# 3-21.net
KiCad netlist of a schematic drawn in Altium Designer
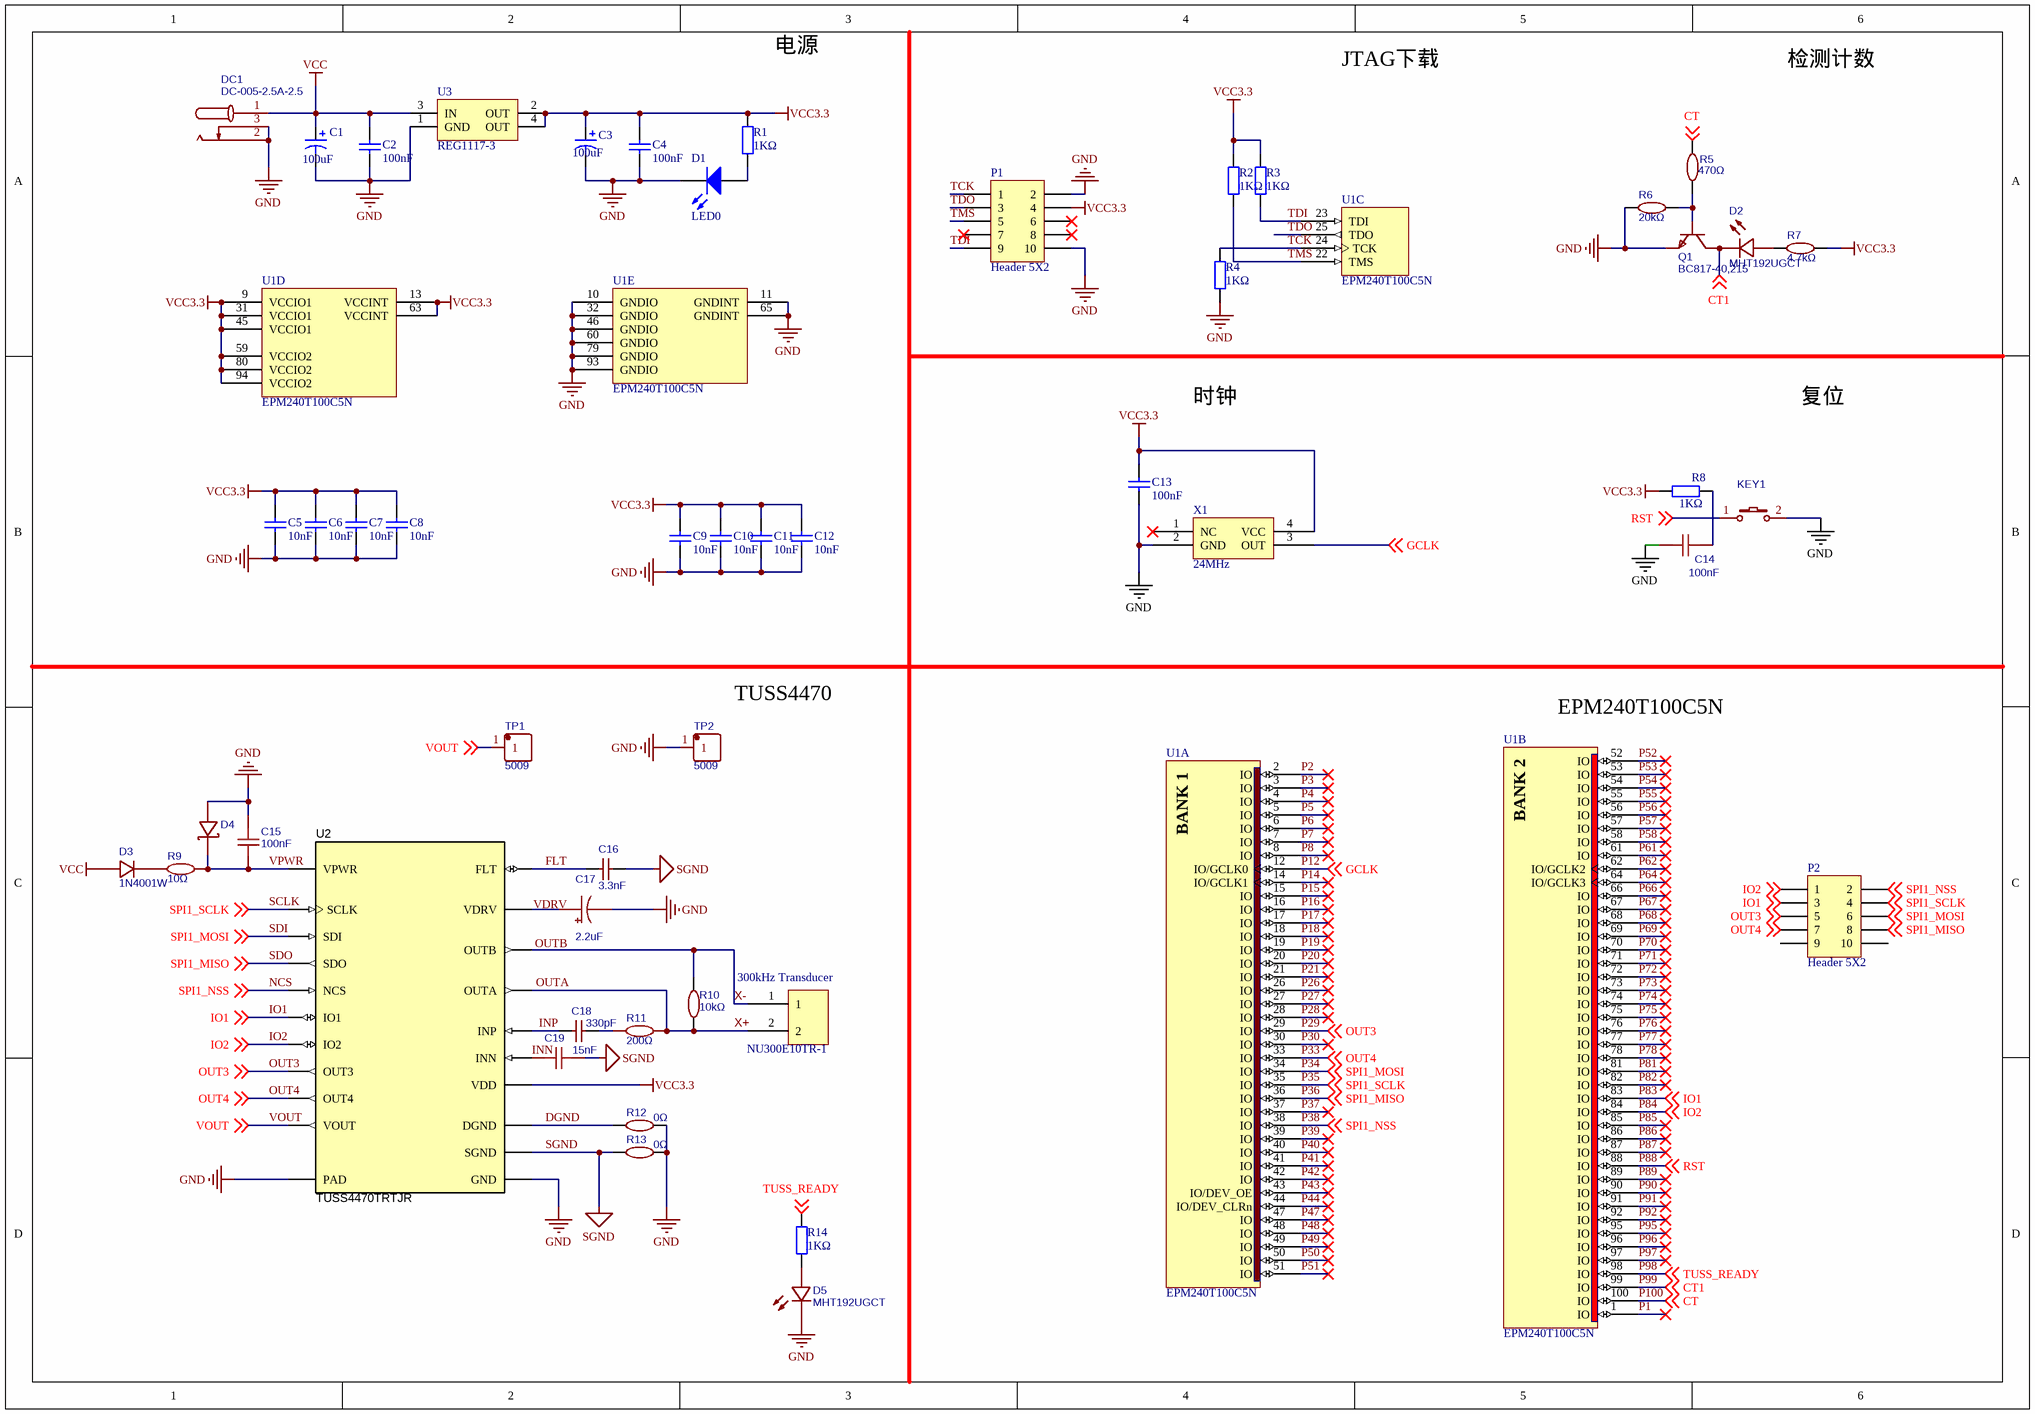
[diagram p0: 超声波接近电路3-21.SchDoc]

(export (version "E")
  (design (tool "Eeschema 10.0.6"))
  (components
    (comp (ref "300kHz Transducer")
      (value "NU300E10TR-1")
      (footprint "NU300E10TR-1")
      (libsource (lib "超声波接近电路") (part "NU300E10TR-1"))
    )
    (comp (ref "C1")
      (value "100uF")
      (footprint "CAP-SMD_L3.2-W1.6-RD")
      (description "Polarized Capacitor (Radial)")
      (fields (field (name "PUBLISHER") "Altium Limited"))
      (libsource (lib "Graduation_Design") (part "100uF_1"))
    )
    (comp (ref "C2")
      (value "100nF")
      (footprint "C0603")
      (description "Capacitor")
      (fields (field (name "PUBLISHER") "Altium Limited"))
      (libsource (lib "Graduation_Design") (part "100nF"))
    )
    (comp (ref "C3")
      (value "100uF")
      (footprint "CAP-SMD_L3.2-W1.6-RD")
      (description "Polarized Capacitor (Radial)")
      (fields (field (name "PUBLISHER") "Altium Limited"))
      (libsource (lib "Graduation_Design") (part "100uF_1"))
    )
    (comp (ref "C4")
      (value "100nF")
      (footprint "C0603")
      (description "Capacitor")
      (fields (field (name "PUBLISHER") "Altium Limited"))
      (libsource (lib "Graduation_Design") (part "100nF"))
    )
    (comp (ref "C5")
      (value "10nF")
      (footprint "C0603")
      (description "Capacitor")
      (fields (field (name "PUBLISHER") "Altium Limited"))
      (libsource (lib "Graduation_Design") (part "10nF"))
    )
    (comp (ref "C6")
      (value "10nF")
      (footprint "C0603")
      (description "Capacitor")
      (fields (field (name "PUBLISHER") "Altium Limited"))
      (libsource (lib "Graduation_Design") (part "10nF"))
    )
    (comp (ref "C7")
      (value "10nF")
      (footprint "C0603")
      (description "Capacitor")
      (fields (field (name "PUBLISHER") "Altium Limited"))
      (libsource (lib "Graduation_Design") (part "10nF"))
    )
    (comp (ref "C8")
      (value "10nF")
      (footprint "C0603")
      (description "Capacitor")
      (fields (field (name "PUBLISHER") "Altium Limited"))
      (libsource (lib "Graduation_Design") (part "10nF"))
    )
    (comp (ref "C9")
      (value "10nF")
      (footprint "C0603")
      (description "Capacitor")
      (fields (field (name "PUBLISHER") "Altium Limited"))
      (libsource (lib "Graduation_Design") (part "10nF"))
    )
    (comp (ref "C10")
      (value "10nF")
      (footprint "C0603")
      (description "Capacitor")
      (fields (field (name "PUBLISHER") "Altium Limited"))
      (libsource (lib "Graduation_Design") (part "10nF"))
    )
    (comp (ref "C11")
      (value "10nF")
      (footprint "C0603")
      (description "Capacitor")
      (fields (field (name "PUBLISHER") "Altium Limited"))
      (libsource (lib "Graduation_Design") (part "10nF"))
    )
    (comp (ref "C12")
      (value "10nF")
      (footprint "C0603")
      (description "Capacitor")
      (fields (field (name "PUBLISHER") "Altium Limited"))
      (libsource (lib "Graduation_Design") (part "10nF"))
    )
    (comp (ref "C13")
      (value "100nF")
      (footprint "C0603")
      (description "Capacitor")
      (fields (field (name "PUBLISHER") "Altium Limited"))
      (libsource (lib "Graduation_Design") (part "100nF"))
    )
    (comp (ref "C14")
      (value "100nF")
      (footprint "C0603")
      (fields (field (name "CONTRIBUTOR") "LCEDA_Lib"))
      (libsource (lib "altium-import") (part "root_2_100nF_"))
    )
    (comp (ref "C15")
      (value "100nF")
      (footprint "C0603")
      (fields
        (field (name "BOM_MANUFACTURER PART") "CC0603KRX7R9BB104")
        (field (name "BOM_SUPPLIER PART") "C14663")
      )
      (libsource (lib "超声波接近电路") (part "100nF"))
    )
    (comp (ref "C16")
      (value "3.3nF")
      (footprint "C0603")
      (fields
        (field (name "BOM_MANUFACTURER PART") "GRM1885C1H332JA01D")
        (field (name "BOM_SUPPLIER PART") "C77036")
      )
      (libsource (lib "超声波接近电路") (part "3.3nF"))
    )
    (comp (ref "C17")
      (value "2.2uF")
      (footprint "CAP-SMD_L3.2-W1.6-RD")
      (fields
        (field (name "BOM_SUPPLIER PART") "C122264")
        (field (name "BOM_MANUFACTURER PART") "T491A225K035AT")
        (field (name "CONTRIBUTOR") "LCSC")
      )
      (libsource (lib "超声波接近电路") (part "2.2uF_1"))
    )
    (comp (ref "C18")
      (value "330pF")
      (footprint "C0603")
      (fields
        (field (name "BOM_MANUFACTURER PART") "CL10C331JB8NNNC")
        (field (name "BOM_SUPPLIER PART") "C1664")
      )
      (libsource (lib "超声波接近电路") (part "330pF"))
    )
    (comp (ref "C19")
      (value "15nF")
      (footprint "C0603")
      (fields
        (field (name "BOM_SUPPLIER PART") "C519550")
        (field (name "BOM_MANUFACTURER PART") "CC0603JRX7R9BB153")
        (field (name "CONTRIBUTOR") "LCSC")
      )
      (libsource (lib "超声波接近电路") (part "15nF"))
    )
    (comp (ref "D1")
      (value "LED0")
      (footprint "LED0603-RD_RED")
      (description "Typical INFRARED GaAs LED")
      (fields (field (name "PUBLISHER") "Altium Limited"))
      (libsource (lib "Miscellaneous Devices") (part "LED0"))
    )
    (comp (ref "D2")
      (value "MHT192UGCT")
      (footprint "LED0603-RD_GREEN")
      (fields (field (name "BOM_SUPPLIER PART") "C389519") (field (name "CONTRIBUTOR") "LCSC"))
      (libsource (lib "Graduation_Design") (part "MHT192UGCT"))
    )
    (comp (ref "D3")
      (value "1N4001W")
      (footprint "SOD-123F_L2.8-W1.8-LS3.7-RD")
      (fields (field (name "BOM_SUPPLIER PART") "C162732") (field (name "CONTRIBUTOR") "LCSC"))
      (libsource (lib "超声波接近电路") (part "1N4001W"))
    )
    (comp (ref "D4")
      (value "SMF36A_C353286")
      (footprint "SOD-123FL_L2.7-W1.8-LS3.8-RD")
      (fields
        (field (name "BOM_SUPPLIER PART") "C353286")
        (field (name "BOM_MANUFACTURER PART") "SMF36A")
        (field (name "CONTRIBUTOR") "LCSC")
      )
      (libsource (lib "超声波接近电路") (part "SMF36A_C353286"))
    )
    (comp (ref "D5")
      (value "MHT192UGCT")
      (footprint "LED0603-RD_GREEN")
      (fields (field (name "BOM_SUPPLIER PART") "C389519") (field (name "CONTRIBUTOR") "LCSC"))
      (libsource (lib "Graduation_Design") (part "MHT192UGCT"))
    )
    (comp (ref "DC1")
      (value "DC-005-2.5A-2.5")
      (footprint "CONN-TH_DC-005-2.5A-2.0")
      (fields (field (name "BOM_SUPPLIER PART") "C319098") (field (name "CONTRIBUTOR") "LCSC"))
      (libsource (lib "altium-import") (part "root_0_DC-005-2.5A-2.5_"))
    )
    (comp (ref "KEY1")
      (value "K2-3.6×6.1_SMD")
      (footprint "KEY-SMD_2P-L6.2-W3.6-LS8.0")
      (fields
        (field (name "BOM_SUPPLIER PART") "C118141")
        (field (name "BOM_MANUFACTURER PART") "K2-1107ST-A4SW-06")
        (field (name "CONTRIBUTOR") "LCEDA_Lib")
      )
      (libsource (lib "altium-import") (part "root_0_K2-3.6×6.1_SMD_"))
    )
    (comp (ref "P1")
      (value "Header 5X2")
      (footprint "HDR2X5")
      (description "Header, 5-Pin, Dual row")
      (fields (field (name "PUBLISHER") "Altium Limited"))
      (libsource (lib "Miscellaneous Connectors") (part "Header 5X2"))
    )
    (comp (ref "P2")
      (value "Header 5X2")
      (footprint "HDR2X5")
      (description "Header, 5-Pin, Dual row")
      (fields (field (name "PUBLISHER") "Altium Limited"))
      (libsource (lib "Miscellaneous Connectors") (part "Header 5X2"))
    )
    (comp (ref "Q1")
      (value "BC817-40,215")
      (footprint "SOT-23-3_L2.9-W1.6-P1.90-LS2.8-BR")
      (fields (field (name "BOM_SUPPLIER PART") "C52801"))
      (libsource (lib "超声波接近电路") (part "BC817-40,215"))
    )
    (comp (ref "R1")
      (value "1KΩ")
      (footprint "R0603")
      (description "Resistor")
      (fields (field (name "PUBLISHER") "Altium Limited"))
      (libsource (lib "Graduation_Design") (part "1KΩ"))
    )
    (comp (ref "R2")
      (value "1KΩ")
      (footprint "R0603")
      (description "Resistor")
      (fields (field (name "PUBLISHER") "Altium Limited"))
      (libsource (lib "Graduation_Design") (part "1KΩ"))
    )
    (comp (ref "R3")
      (value "1KΩ")
      (footprint "R0603")
      (description "Resistor")
      (fields (field (name "PUBLISHER") "Altium Limited"))
      (libsource (lib "Graduation_Design") (part "1KΩ"))
    )
    (comp (ref "R4")
      (value "1KΩ")
      (footprint "R0603")
      (description "Resistor")
      (fields (field (name "PUBLISHER") "Altium Limited"))
      (libsource (lib "Graduation_Design") (part "1KΩ"))
    )
    (comp (ref "R5")
      (value "470Ω")
      (footprint "R0603")
      (fields
        (field (name "BOM_MANUFACTURER PART") "0603WAJ0471T5E")
        (field (name "BOM_SUPPLIER PART") "C25241")
      )
      (libsource (lib "超声波接近电路") (part "470Ω"))
    )
    (comp (ref "R6")
      (value "20kΩ")
      (footprint "R0603")
      (fields
        (field (name "BOM_MANUFACTURER PART") "0603WAF2002T5E")
        (field (name "BOM_SUPPLIER PART") "C4184")
      )
      (libsource (lib "超声波接近电路") (part "20kΩ"))
    )
    (comp (ref "R7")
      (value "4.7kΩ")
      (footprint "R0603")
      (fields
        (field (name "BOM_MANUFACTURER PART") "0603WAF4701T5E")
        (field (name "BOM_SUPPLIER PART") "C23162")
      )
      (libsource (lib "超声波接近电路") (part "4.7kΩ"))
    )
    (comp (ref "R8")
      (value "1KΩ")
      (footprint "R0603")
      (description "Resistor")
      (fields (field (name "PUBLISHER") "Altium Limited"))
      (libsource (lib "") (part "1KΩ_1"))
    )
    (comp (ref "R9")
      (value "10Ω")
      (footprint "R0603")
      (fields
        (field (name "BOM_SUPPLIER PART") "C441879")
        (field (name "BOM_MANUFACTURER PART") "ERJPA3J100V")
        (field (name "CONTRIBUTOR") "LCSC")
      )
      (libsource (lib "超声波接近电路") (part "10Ω"))
    )
    (comp (ref "R10")
      (value "10kΩ")
      (footprint "R0603")
      (fields
        (field (name "BOM_MANUFACTURER PART") "0603WAF1002T5E")
        (field (name "BOM_SUPPLIER PART") "C25804")
      )
      (libsource (lib "超声波接近电路") (part "10kΩ"))
    )
    (comp (ref "R11")
      (value "200Ω")
      (footprint "R0603")
      (fields
        (field (name "BOM_SUPPLIER PART") "C254528")
        (field (name "BOM_MANUFACTURER PART") "ERJ-PA3F2000V")
        (field (name "CONTRIBUTOR") "LCSC")
      )
      (libsource (lib "超声波接近电路") (part "200Ω"))
    )
    (comp (ref "R12")
      (value "0Ω")
      (footprint "R0603")
      (fields
        (field (name "BOM_MANUFACTURER PART") "RC0603JR-070RL")
        (field (name "BOM_SUPPLIER PART") "C95177")
      )
      (libsource (lib "超声波接近电路") (part "0_1"))
    )
    (comp (ref "R13")
      (value "0Ω")
      (footprint "R0603")
      (fields
        (field (name "BOM_MANUFACTURER PART") "RC0603JR-070RL")
        (field (name "BOM_SUPPLIER PART") "C95177")
      )
      (libsource (lib "超声波接近电路") (part "0_1"))
    )
    (comp (ref "R14")
      (value "1KΩ")
      (footprint "R0603")
      (description "Resistor")
      (fields (field (name "PUBLISHER") "Altium Limited"))
      (libsource (lib "Graduation_Design") (part "1KΩ"))
    )
    (comp (ref "TP1")
      (value "5009")
      (footprint "TEST-TH_BD3.18-P1.93")
      (fields (field (name "BOM_SUPPLIER PART") "C238126") (field (name "CONTRIBUTOR") "LCSC"))
      (libsource (lib "超声波接近电路") (part "5009"))
    )
    (comp (ref "TP2")
      (value "5009")
      (footprint "TEST-TH_BD3.18-P1.93")
      (fields (field (name "BOM_SUPPLIER PART") "C238126") (field (name "CONTRIBUTOR") "LCSC"))
      (libsource (lib "超声波接近电路") (part "5009"))
    )
    (comp (ref "U1")
      (value "EPM240T100C5N")
      (footprint "TQFP-100_L14.0-W14.0-P0.50-LS16.0-BL")
      (fields (field (name "PUBLISHER") "Altium Limited"))
      (libsource (lib "CPLD实验板") (part "EPM240T100C5N"))
    )
    (comp (ref "U2")
      (value "TUSS4470TRTJR")
      (footprint "QFN-20_L4.0-W4.0-P0.50-TL-EP2.7")
      (description "Ultrasonic Sensor Signal Conditioner IC for Directly")
      (fields
        (field (name "MANUFACTURER") "Texas Instruments")
        (field (name "ALTERNATE PARTNUMBER") "PGA44801RTJT")
      )
      (libsource (lib "Graduation_Design") (part "CMP-0081414-4"))
    )
    (comp (ref "U3")
      (value "REG1117-3")
      (footprint "ZZ311")
      (description "800mA Low Dropout Positive Regulator Fixed 2.85V,3V,3.3V and 5V")
      (fields (field (name "PUBLISHER") "Altium Limited"))
      (libsource (lib "BB Power Mgt Voltage Regulator") (part "REG1117-3"))
    )
    (comp (ref "X1")
      (value "24MHz")
      (footprint "OSC-SMD_4P-L7.0-W5.0-BL_SIT1602")
      (libsource (lib "Schlib1") (part "oscillator"))
    )
  )
  (nets
    (net (code "1") (name "/DGND") (class "Default")
      (node (ref "R12") (pin "1") (pinfunction "1_1") (pintype "passive"))
      (node (ref "U2") (pin "2") (pinfunction "DGND_2") (pintype "power_in"))
    )
    (net (code "2") (name "/FLT") (class "Default")
      (node (ref "C16") (pin "1") (pinfunction "1_1") (pintype "passive"))
      (node (ref "U2") (pin "18") (pinfunction "FLT_18") (pintype "bidirectional"))
    )
    (net (code "3") (name "/INN") (class "Default")
      (node (ref "C19") (pin "1") (pinfunction "1_1") (pintype "passive"))
      (node (ref "U2") (pin "11") (pinfunction "INN_11") (pintype "input"))
    )
    (net (code "4") (name "/INP") (class "Default")
      (node (ref "C18") (pin "1") (pinfunction "1_1") (pintype "passive"))
      (node (ref "U2") (pin "12") (pinfunction "INP_12") (pintype "input"))
    )
    (net (code "5") (name "/OUTA") (class "Default")
      (node (ref "300kHz Transducer") (pin "2") (pinfunction "2_2") (pintype "passive"))
      (node (ref "R10") (pin "1") (pinfunction "1_1") (pintype "passive"))
      (node (ref "R11") (pin "2") (pinfunction "2_2") (pintype "passive"))
      (node (ref "U2") (pin "15") (pinfunction "OUTA_15") (pintype "output"))
    )
    (net (code "7") (name "/P1") (class "Default")
      (node (ref "U1") (pin "1") (pinfunction "IO_1") (pintype "bidirectional+no_connect"))
    )
    (net (code "8") (name "/P2") (class "Default")
      (node (ref "U1") (pin "2") (pinfunction "IO_2") (pintype "bidirectional+no_connect"))
    )
    (net (code "9") (name "/P3") (class "Default")
      (node (ref "U1") (pin "3") (pinfunction "IO_3") (pintype "bidirectional+no_connect"))
    )
    (net (code "10") (name "/P4") (class "Default")
      (node (ref "U1") (pin "4") (pinfunction "IO_4") (pintype "bidirectional+no_connect"))
    )
    (net (code "11") (name "/P5") (class "Default")
      (node (ref "U1") (pin "5") (pinfunction "IO_5") (pintype "bidirectional+no_connect"))
    )
    (net (code "12") (name "/P6") (class "Default")
      (node (ref "U1") (pin "6") (pinfunction "IO_6") (pintype "bidirectional+no_connect"))
    )
    (net (code "13") (name "/P7") (class "Default")
      (node (ref "U1") (pin "7") (pinfunction "IO_7") (pintype "bidirectional+no_connect"))
    )
    (net (code "14") (name "/P8") (class "Default")
      (node (ref "U1") (pin "8") (pinfunction "IO_8") (pintype "bidirectional+no_connect"))
    )
    (net (code "15") (name "/P14") (class "Default")
      (node (ref "U1") (pin "14") (pinfunction "IO/GCLK1_14") (pintype "bidirectional+no_connect"))
    )
    (net (code "16") (name "/P15") (class "Default")
      (node (ref "U1") (pin "15") (pinfunction "IO_15") (pintype "bidirectional+no_connect"))
    )
    (net (code "17") (name "/P16") (class "Default")
      (node (ref "U1") (pin "16") (pinfunction "IO_16") (pintype "bidirectional+no_connect"))
    )
    (net (code "18") (name "/P17") (class "Default")
      (node (ref "U1") (pin "17") (pinfunction "IO_17") (pintype "bidirectional+no_connect"))
    )
    (net (code "19") (name "/P18") (class "Default")
      (node (ref "U1") (pin "18") (pinfunction "IO_18") (pintype "bidirectional+no_connect"))
    )
    (net (code "20") (name "/P19") (class "Default")
      (node (ref "U1") (pin "19") (pinfunction "IO_19") (pintype "bidirectional+no_connect"))
    )
    (net (code "21") (name "/P20") (class "Default")
      (node (ref "U1") (pin "20") (pinfunction "IO_20") (pintype "bidirectional+no_connect"))
    )
    (net (code "22") (name "/P21") (class "Default")
      (node (ref "U1") (pin "21") (pinfunction "IO_21") (pintype "bidirectional+no_connect"))
    )
    (net (code "23") (name "/P26") (class "Default")
      (node (ref "U1") (pin "26") (pinfunction "IO_26") (pintype "bidirectional+no_connect"))
    )
    (net (code "24") (name "/P27") (class "Default")
      (node (ref "U1") (pin "27") (pinfunction "IO_27") (pintype "bidirectional+no_connect"))
    )
    (net (code "25") (name "/P28") (class "Default")
      (node (ref "U1") (pin "28") (pinfunction "IO_28") (pintype "bidirectional+no_connect"))
    )
    (net (code "26") (name "/P30") (class "Default")
      (node (ref "U1") (pin "30") (pinfunction "IO_30") (pintype "bidirectional+no_connect"))
    )
    (net (code "27") (name "/P37") (class "Default")
      (node (ref "U1") (pin "37") (pinfunction "IO_37") (pintype "bidirectional+no_connect"))
    )
    (net (code "28") (name "/P39") (class "Default")
      (node (ref "U1") (pin "39") (pinfunction "IO_39") (pintype "bidirectional+no_connect"))
    )
    (net (code "29") (name "/P40") (class "Default")
      (node (ref "U1") (pin "40") (pinfunction "IO_40") (pintype "bidirectional+no_connect"))
    )
    (net (code "30") (name "/P41") (class "Default")
      (node (ref "U1") (pin "41") (pinfunction "IO_41") (pintype "bidirectional+no_connect"))
    )
    (net (code "31") (name "/P42") (class "Default")
      (node (ref "U1") (pin "42") (pinfunction "IO_42") (pintype "bidirectional+no_connect"))
    )
    (net (code "32") (name "/P43") (class "Default")
      (node (ref "U1") (pin "43") (pinfunction "IO/DEV_OE_43") (pintype "bidirectional+no_connect"))
    )
    (net (code "33") (name "/P44") (class "Default")
      (node (ref "U1") (pin "44") (pinfunction "IO/DEV_CLRn_44") (pintype "bidirectional+no_connect"))
    )
    (net (code "34") (name "/P47") (class "Default")
      (node (ref "U1") (pin "47") (pinfunction "IO_47") (pintype "bidirectional+no_connect"))
    )
    (net (code "35") (name "/P48") (class "Default")
      (node (ref "U1") (pin "48") (pinfunction "IO_48") (pintype "bidirectional+no_connect"))
    )
    (net (code "36") (name "/P49") (class "Default")
      (node (ref "U1") (pin "49") (pinfunction "IO_49") (pintype "bidirectional+no_connect"))
    )
    (net (code "37") (name "/P50") (class "Default")
      (node (ref "U1") (pin "50") (pinfunction "IO_50") (pintype "bidirectional+no_connect"))
    )
    (net (code "38") (name "/P51") (class "Default")
      (node (ref "U1") (pin "51") (pinfunction "IO_51") (pintype "bidirectional+no_connect"))
    )
    (net (code "39") (name "/P52") (class "Default")
      (node (ref "U1") (pin "52") (pinfunction "IO_52") (pintype "bidirectional+no_connect"))
    )
    (net (code "40") (name "/P53") (class "Default")
      (node (ref "U1") (pin "53") (pinfunction "IO_53") (pintype "bidirectional+no_connect"))
    )
    (net (code "41") (name "/P54") (class "Default")
      (node (ref "U1") (pin "54") (pinfunction "IO_54") (pintype "bidirectional+no_connect"))
    )
    (net (code "42") (name "/P55") (class "Default")
      (node (ref "U1") (pin "55") (pinfunction "IO_55") (pintype "bidirectional+no_connect"))
    )
    (net (code "43") (name "/P56") (class "Default")
      (node (ref "U1") (pin "56") (pinfunction "IO_56") (pintype "bidirectional+no_connect"))
    )
    (net (code "44") (name "/P57") (class "Default")
      (node (ref "U1") (pin "57") (pinfunction "IO_57") (pintype "bidirectional+no_connect"))
    )
    (net (code "45") (name "/P58") (class "Default")
      (node (ref "U1") (pin "58") (pinfunction "IO_58") (pintype "bidirectional+no_connect"))
    )
    (net (code "46") (name "/P61") (class "Default")
      (node (ref "U1") (pin "61") (pinfunction "IO_61") (pintype "bidirectional+no_connect"))
    )
    (net (code "47") (name "/P62") (class "Default")
      (node (ref "U1") (pin "62") (pinfunction "IO/GCLK2_62") (pintype "bidirectional+no_connect"))
    )
    (net (code "48") (name "/P64") (class "Default")
      (node (ref "U1") (pin "64") (pinfunction "IO/GCLK3_64") (pintype "bidirectional+no_connect"))
    )
    (net (code "49") (name "/P66") (class "Default")
      (node (ref "U1") (pin "66") (pinfunction "IO_66") (pintype "bidirectional+no_connect"))
    )
    (net (code "50") (name "/P67") (class "Default")
      (node (ref "U1") (pin "67") (pinfunction "IO_67") (pintype "bidirectional+no_connect"))
    )
    (net (code "51") (name "/P68") (class "Default")
      (node (ref "U1") (pin "68") (pinfunction "IO_68") (pintype "bidirectional+no_connect"))
    )
    (net (code "52") (name "/P69") (class "Default")
      (node (ref "U1") (pin "69") (pinfunction "IO_69") (pintype "bidirectional+no_connect"))
    )
    (net (code "53") (name "/P70") (class "Default")
      (node (ref "U1") (pin "70") (pinfunction "IO_70") (pintype "bidirectional+no_connect"))
    )
    (net (code "54") (name "/P71") (class "Default")
      (node (ref "U1") (pin "71") (pinfunction "IO_71") (pintype "bidirectional+no_connect"))
    )
    (net (code "55") (name "/P72") (class "Default")
      (node (ref "U1") (pin "72") (pinfunction "IO_72") (pintype "bidirectional+no_connect"))
    )
    (net (code "56") (name "/P73") (class "Default")
      (node (ref "U1") (pin "73") (pinfunction "IO_73") (pintype "bidirectional+no_connect"))
    )
    (net (code "57") (name "/P74") (class "Default")
      (node (ref "U1") (pin "74") (pinfunction "IO_74") (pintype "bidirectional+no_connect"))
    )
    (net (code "58") (name "/P75") (class "Default")
      (node (ref "U1") (pin "75") (pinfunction "IO_75") (pintype "bidirectional+no_connect"))
    )
    (net (code "59") (name "/P76") (class "Default")
      (node (ref "U1") (pin "76") (pinfunction "IO_76") (pintype "bidirectional+no_connect"))
    )
    (net (code "60") (name "/P77") (class "Default")
      (node (ref "U1") (pin "77") (pinfunction "IO_77") (pintype "bidirectional+no_connect"))
    )
    (net (code "61") (name "/P78") (class "Default")
      (node (ref "U1") (pin "78") (pinfunction "IO_78") (pintype "bidirectional+no_connect"))
    )
    (net (code "62") (name "/P81") (class "Default")
      (node (ref "U1") (pin "81") (pinfunction "IO_81") (pintype "bidirectional+no_connect"))
    )
    (net (code "63") (name "/P82") (class "Default")
      (node (ref "U1") (pin "82") (pinfunction "IO_82") (pintype "bidirectional+no_connect"))
    )
    (net (code "64") (name "/P85") (class "Default")
      (node (ref "U1") (pin "85") (pinfunction "IO_85") (pintype "bidirectional+no_connect"))
    )
    (net (code "65") (name "/P86") (class "Default")
      (node (ref "U1") (pin "86") (pinfunction "IO_86") (pintype "bidirectional+no_connect"))
    )
    (net (code "66") (name "/P87") (class "Default")
      (node (ref "U1") (pin "87") (pinfunction "IO_87") (pintype "bidirectional+no_connect"))
    )
    (net (code "67") (name "/P89") (class "Default")
      (node (ref "U1") (pin "89") (pinfunction "IO_89") (pintype "bidirectional+no_connect"))
    )
    (net (code "68") (name "/P90") (class "Default")
      (node (ref "U1") (pin "90") (pinfunction "IO_90") (pintype "bidirectional+no_connect"))
    )
    (net (code "69") (name "/P91") (class "Default")
      (node (ref "U1") (pin "91") (pinfunction "IO_91") (pintype "bidirectional+no_connect"))
    )
    (net (code "70") (name "/P92") (class "Default")
      (node (ref "U1") (pin "92") (pinfunction "IO_92") (pintype "bidirectional+no_connect"))
    )
    (net (code "71") (name "/P95") (class "Default")
      (node (ref "U1") (pin "95") (pinfunction "IO_95") (pintype "bidirectional+no_connect"))
    )
    (net (code "72") (name "/P96") (class "Default")
      (node (ref "U1") (pin "96") (pinfunction "IO_96") (pintype "bidirectional+no_connect"))
    )
    (net (code "73") (name "/P97") (class "Default")
      (node (ref "U1") (pin "97") (pinfunction "IO_97") (pintype "bidirectional+no_connect"))
    )
    (net (code "74") (name "/TCK") (class "Default")
      (node (ref "P1") (pin "1") (pinfunction "1_1") (pintype "passive"))
      (node (ref "R4") (pin "2") (pinfunction "2_2") (pintype "passive"))
      (node (ref "U1") (pin "24") (pinfunction "TCK_24") (pintype "input"))
    )
    (net (code "75") (name "/TDI") (class "Default")
      (node (ref "P1") (pin "9") (pinfunction "9_9") (pintype "passive"))
      (node (ref "R3") (pin "1") (pinfunction "1_1") (pintype "passive"))
      (node (ref "U1") (pin "23") (pinfunction "TDI_23") (pintype "input"))
    )
    (net (code "76") (name "/TDO") (class "Default")
      (node (ref "P1") (pin "3") (pinfunction "3_3") (pintype "passive"))
      (node (ref "U1") (pin "25") (pinfunction "TDO_25") (pintype "output"))
    )
    (net (code "77") (name "/TMS") (class "Default")
      (node (ref "P1") (pin "5") (pinfunction "5_5") (pintype "passive"))
      (node (ref "R2") (pin "1") (pinfunction "1_1") (pintype "passive"))
      (node (ref "U1") (pin "22") (pinfunction "TMS_22") (pintype "input"))
    )
    (net (code "79") (name "/VPWR") (class "Default")
      (node (ref "C15") (pin "1") (pinfunction "1_1") (pintype "passive"))
      (node (ref "D4") (pin "1") (pinfunction "K_1") (pintype "passive"))
      (node (ref "R9") (pin "2") (pinfunction "2_2") (pintype "passive"))
      (node (ref "U2") (pin "20") (pinfunction "VPWR_20") (pintype "power_in"))
    )
    (net (code "80") (name "/X-") (class "Default")
      (node (ref "300kHz Transducer") (pin "1") (pinfunction "1_1") (pintype "passive"))
      (node (ref "R10") (pin "2") (pinfunction "2_2") (pintype "passive"))
      (node (ref "U2") (pin "16") (pinfunction "OUTB_16") (pintype "output"))
    )
    (net (code "81") (name "CT") (class "Default")
      (node (ref "R5") (pin "1") (pinfunction "1_1") (pintype "passive"))
      (node (ref "U1") (pin "100") (pinfunction "IO_100") (pintype "bidirectional"))
    )
    (net (code "82") (name "CT1") (class "Default")
      (node (ref "D2") (pin "1") (pinfunction "-_1") (pintype "passive"))
      (node (ref "Q1") (pin "3") (pinfunction "3_3") (pintype "passive"))
      (node (ref "U1") (pin "99") (pinfunction "IO_99") (pintype "bidirectional"))
    )
    (net (code "83") (name "GCLK") (class "Default")
      (node (ref "U1") (pin "12") (pinfunction "IO/GCLK0_12") (pintype "bidirectional"))
      (node (ref "X1") (pin "3") (pinfunction "OUT_3") (pintype "passive"))
    )
    (net (code "84") (name "GND") (class "Default")
      (node (ref "C1") (pin "2") (pinfunction "2_2") (pintype "passive"))
      (node (ref "C10") (pin "1") (pinfunction "1_1") (pintype "passive"))
      (node (ref "C11") (pin "1") (pinfunction "1_1") (pintype "passive"))
      (node (ref "C12") (pin "1") (pinfunction "1_1") (pintype "passive"))
      (node (ref "C13") (pin "1") (pinfunction "1_1") (pintype "passive"))
      (node (ref "C14") (pin "2") (pinfunction "2_2") (pintype "passive"))
      (node (ref "C15") (pin "2") (pinfunction "2_2") (pintype "passive"))
      (node (ref "C17") (pin "2") (pinfunction "2_2") (pintype "passive"))
      (node (ref "C2") (pin "2") (pinfunction "2_2") (pintype "passive"))
      (node (ref "C3") (pin "2") (pinfunction "2_2") (pintype "passive"))
      (node (ref "C4") (pin "2") (pinfunction "2_2") (pintype "passive"))
      (node (ref "C5") (pin "1") (pinfunction "1_1") (pintype "passive"))
      (node (ref "C6") (pin "1") (pinfunction "1_1") (pintype "passive"))
      (node (ref "C7") (pin "1") (pinfunction "1_1") (pintype "passive"))
      (node (ref "C8") (pin "1") (pinfunction "1_1") (pintype "passive"))
      (node (ref "C9") (pin "1") (pinfunction "1_1") (pintype "passive"))
      (node (ref "D1") (pin "2") (pinfunction "K_2") (pintype "passive"))
      (node (ref "D4") (pin "2") (pinfunction "A_2") (pintype "passive"))
      (node (ref "D5") (pin "1") (pinfunction "-_1") (pintype "passive"))
      (node (ref "DC1") (pin "2") (pinfunction "2_2") (pintype "passive"))
      (node (ref "DC1") (pin "3") (pinfunction "3_3") (pintype "passive"))
      (node (ref "KEY1") (pin "2") (pinfunction "2_2") (pintype "passive"))
      (node (ref "P1") (pin "10") (pinfunction "10_10") (pintype "passive"))
      (node (ref "P1") (pin "2") (pinfunction "2_2") (pintype "passive"))
      (node (ref "Q1") (pin "2") (pinfunction "2_2") (pintype "passive"))
      (node (ref "R12") (pin "2") (pinfunction "2_2") (pintype "passive"))
      (node (ref "R13") (pin "2") (pinfunction "2_2") (pintype "passive"))
      (node (ref "R4") (pin "1") (pinfunction "1_1") (pintype "passive"))
      (node (ref "R6") (pin "1") (pinfunction "1_1") (pintype "passive"))
      (node (ref "TP2") (pin "1") (pinfunction "1_1") (pintype "passive"))
      (node (ref "U1") (pin "10") (pinfunction "GNDIO_10") (pintype "power_in"))
      (node (ref "U1") (pin "11") (pinfunction "GNDINT_11") (pintype "power_in"))
      (node (ref "U1") (pin "32") (pinfunction "GNDIO_32") (pintype "power_in"))
      (node (ref "U1") (pin "46") (pinfunction "GNDIO_46") (pintype "power_in"))
      (node (ref "U1") (pin "60") (pinfunction "GNDIO_60") (pintype "power_in"))
      (node (ref "U1") (pin "65") (pinfunction "GNDINT_65") (pintype "power_in"))
      (node (ref "U1") (pin "79") (pinfunction "GNDIO_79") (pintype "power_in"))
      (node (ref "U1") (pin "93") (pinfunction "GNDIO_93") (pintype "power_in"))
      (node (ref "U2") (pin "14") (pinfunction "GND_14") (pintype "power_in"))
      (node (ref "U2") (pin "21") (pinfunction "PAD_21") (pintype "passive"))
      (node (ref "U3") (pin "1") (pinfunction "GND_1") (pintype "power_in"))
      (node (ref "X1") (pin "2") (pinfunction "GND_2") (pintype "passive"))
    )
    (net (code "85") (name "IO1") (class "Default")
      (node (ref "P2") (pin "3") (pinfunction "3_3") (pintype "passive"))
      (node (ref "U1") (pin "83") (pinfunction "IO_83") (pintype "bidirectional"))
      (node (ref "U2") (pin "7") (pinfunction "IO1_7") (pintype "bidirectional"))
    )
    (net (code "86") (name "IO2") (class "Default")
      (node (ref "P2") (pin "1") (pinfunction "1_1") (pintype "passive"))
      (node (ref "U1") (pin "84") (pinfunction "IO_84") (pintype "bidirectional"))
      (node (ref "U2") (pin "8") (pinfunction "IO2_8") (pintype "bidirectional"))
    )
    (net (code "87") (name "Net-(C14-Pad1)") (class "Default")
      (node (ref "C14") (pin "1") (pinfunction "1_1") (pintype "passive"))
      (node (ref "R8") (pin "1") (pinfunction "1_1") (pintype "passive"))
    )
    (net (code "88") (name "Net-(C18-Pad2)") (class "Default")
      (node (ref "C18") (pin "2") (pinfunction "2_2") (pintype "passive"))
      (node (ref "R11") (pin "1") (pinfunction "1_1") (pintype "passive"))
    )
    (net (code "89") (name "Net-(D1-A)") (class "Default")
      (node (ref "D1") (pin "1") (pinfunction "A_1") (pintype "passive"))
      (node (ref "R1") (pin "1") (pinfunction "1_1") (pintype "passive"))
    )
    (net (code "90") (name "Net-(D2-+)") (class "Default")
      (node (ref "D2") (pin "2") (pinfunction "+_2") (pintype "passive"))
      (node (ref "R7") (pin "1") (pinfunction "1_1") (pintype "passive"))
    )
    (net (code "91") (name "Net-(D3-C)") (class "Default")
      (node (ref "D3") (pin "1") (pinfunction "C_1") (pintype "passive"))
      (node (ref "R9") (pin "1") (pinfunction "1_1") (pintype "passive"))
    )
    (net (code "92") (name "Net-(D5-+)") (class "Default")
      (node (ref "D5") (pin "2") (pinfunction "+_2") (pintype "passive"))
      (node (ref "R14") (pin "1") (pinfunction "1_1") (pintype "passive"))
    )
    (net (code "93") (name "Net-(Q1-Pad1)") (class "Default")
      (node (ref "Q1") (pin "1") (pinfunction "1_1") (pintype "passive"))
      (node (ref "R5") (pin "2") (pinfunction "2_2") (pintype "passive"))
      (node (ref "R6") (pin "2") (pinfunction "2_2") (pintype "passive"))
    )
    (net (code "94") (name "Net-(U2-VDRV)") (class "Default")
      (node (ref "C17") (pin "1") (pinfunction "1_1") (pintype "passive"))
      (node (ref "U2") (pin "17") (pinfunction "VDRV_17") (pintype "power_in"))
    )
    (net (code "95") (name "OUT3") (class "Default")
      (node (ref "P2") (pin "5") (pinfunction "5_5") (pintype "passive"))
      (node (ref "U1") (pin "29") (pinfunction "IO_29") (pintype "bidirectional"))
      (node (ref "U2") (pin "1") (pinfunction "OUT3_1") (pintype "output"))
    )
    (net (code "96") (name "OUT4") (class "Default")
      (node (ref "P2") (pin "7") (pinfunction "7_7") (pintype "passive"))
      (node (ref "U1") (pin "33") (pinfunction "IO_33") (pintype "bidirectional"))
      (node (ref "U2") (pin "19") (pinfunction "OUT4_19") (pintype "output"))
    )
    (net (code "97") (name "RST") (class "Default")
      (node (ref "KEY1") (pin "1") (pinfunction "1_1") (pintype "passive"))
      (node (ref "U1") (pin "88") (pinfunction "IO_88") (pintype "bidirectional"))
    )
    (net (code "98") (name "SGND") (class "Default")
      (node (ref "C16") (pin "2") (pinfunction "2_2") (pintype "passive"))
      (node (ref "C19") (pin "2") (pinfunction "2_2") (pintype "passive"))
      (node (ref "R13") (pin "1") (pinfunction "1_1") (pintype "passive"))
      (node (ref "U2") (pin "13") (pinfunction "SGND_13") (pintype "power_in"))
    )
    (net (code "99") (name "SPI1_MISO") (class "Default")
      (node (ref "P2") (pin "8") (pinfunction "8_8") (pintype "passive"))
      (node (ref "U1") (pin "36") (pinfunction "IO_36") (pintype "bidirectional"))
      (node (ref "U2") (pin "6") (pinfunction "SDO_6") (pintype "output"))
    )
    (net (code "100") (name "SPI1_MOSI") (class "Default")
      (node (ref "P2") (pin "6") (pinfunction "6_6") (pintype "passive"))
      (node (ref "U1") (pin "34") (pinfunction "IO_34") (pintype "bidirectional"))
      (node (ref "U2") (pin "5") (pinfunction "SDI_5") (pintype "input"))
    )
    (net (code "101") (name "SPI1_NSS") (class "Default")
      (node (ref "P2") (pin "2") (pinfunction "2_2") (pintype "passive"))
      (node (ref "U1") (pin "38") (pinfunction "IO_38") (pintype "bidirectional"))
      (node (ref "U2") (pin "3") (pinfunction "NCS_3") (pintype "input"))
    )
    (net (code "102") (name "SPI1_SCLK") (class "Default")
      (node (ref "P2") (pin "4") (pinfunction "4_4") (pintype "passive"))
      (node (ref "U1") (pin "35") (pinfunction "IO_35") (pintype "bidirectional"))
      (node (ref "U2") (pin "4") (pinfunction "SCLK_4") (pintype "input"))
    )
    (net (code "103") (name "TUSS_READY") (class "Default")
      (node (ref "R14") (pin "2") (pinfunction "2_2") (pintype "passive"))
      (node (ref "U1") (pin "98") (pinfunction "IO_98") (pintype "bidirectional"))
    )
    (net (code "104") (name "VCC") (class "Default")
      (node (ref "C1") (pin "1") (pinfunction "1_1") (pintype "passive"))
      (node (ref "C2") (pin "1") (pinfunction "1_1") (pintype "passive"))
      (node (ref "D3") (pin "2") (pinfunction "A_2") (pintype "passive"))
      (node (ref "DC1") (pin "1") (pinfunction "1_1") (pintype "passive"))
      (node (ref "U3") (pin "3") (pinfunction "IN_3") (pintype "power_in"))
    )
    (net (code "105") (name "VCC3.3") (class "Default")
      (node (ref "C10") (pin "2") (pinfunction "2_2") (pintype "passive"))
      (node (ref "C11") (pin "2") (pinfunction "2_2") (pintype "passive"))
      (node (ref "C12") (pin "2") (pinfunction "2_2") (pintype "passive"))
      (node (ref "C13") (pin "2") (pinfunction "2_2") (pintype "passive"))
      (node (ref "C3") (pin "1") (pinfunction "1_1") (pintype "passive"))
      (node (ref "C4") (pin "1") (pinfunction "1_1") (pintype "passive"))
      (node (ref "C5") (pin "2") (pinfunction "2_2") (pintype "passive"))
      (node (ref "C6") (pin "2") (pinfunction "2_2") (pintype "passive"))
      (node (ref "C7") (pin "2") (pinfunction "2_2") (pintype "passive"))
      (node (ref "C8") (pin "2") (pinfunction "2_2") (pintype "passive"))
      (node (ref "C9") (pin "2") (pinfunction "2_2") (pintype "passive"))
      (node (ref "P1") (pin "4") (pinfunction "4_4") (pintype "passive"))
      (node (ref "R1") (pin "2") (pinfunction "2_2") (pintype "passive"))
      (node (ref "R2") (pin "2") (pinfunction "2_2") (pintype "passive"))
      (node (ref "R3") (pin "2") (pinfunction "2_2") (pintype "passive"))
      (node (ref "R7") (pin "2") (pinfunction "2_2") (pintype "passive"))
      (node (ref "R8") (pin "2") (pinfunction "2_2") (pintype "passive"))
      (node (ref "U1") (pin "13") (pinfunction "VCCINT_13") (pintype "power_in"))
      (node (ref "U1") (pin "31") (pinfunction "VCCIO1_31") (pintype "power_in"))
      (node (ref "U1") (pin "45") (pinfunction "VCCIO1_45") (pintype "power_in"))
      (node (ref "U1") (pin "59") (pinfunction "VCCIO2_59") (pintype "power_in"))
      (node (ref "U1") (pin "63") (pinfunction "VCCINT_63") (pintype "power_in"))
      (node (ref "U1") (pin "80") (pinfunction "VCCIO2_80") (pintype "power_in"))
      (node (ref "U1") (pin "9") (pinfunction "VCCIO1_9") (pintype "power_in"))
      (node (ref "U1") (pin "94") (pinfunction "VCCIO2_94") (pintype "power_in"))
      (node (ref "U2") (pin "10") (pinfunction "VDD_10") (pintype "power_in"))
      (node (ref "U3") (pin "2") (pinfunction "OUT_2") (pintype "power_in"))
      (node (ref "U3") (pin "4") (pinfunction "OUT_4") (pintype "power_in"))
      (node (ref "X1") (pin "4") (pinfunction "VCC_4") (pintype "passive"))
    )
    (net (code "106") (name "VOUT") (class "Default")
      (node (ref "TP1") (pin "1") (pinfunction "1_1") (pintype "passive"))
      (node (ref "U2") (pin "9") (pinfunction "VOUT_9") (pintype "output"))
    )
    (net (code "107") (name "unconnected-(P1-Pad6)") (class "Default")
      (node (ref "P1") (pin "6") (pinfunction "6_6") (pintype "passive+no_connect"))
    )
    (net (code "108") (name "unconnected-(P1-Pad7)") (class "Default")
      (node (ref "P1") (pin "7") (pinfunction "7_7") (pintype "passive+no_connect"))
    )
    (net (code "109") (name "unconnected-(P1-Pad8)") (class "Default")
      (node (ref "P1") (pin "8") (pinfunction "8_8") (pintype "passive+no_connect"))
    )
    (net (code "110") (name "unconnected-(P2-Pad9)") (class "Default")
      (node (ref "P2") (pin "9") (pinfunction "9_9") (pintype "passive"))
    )
    (net (code "111") (name "unconnected-(P2-Pad10)") (class "Default")
      (node (ref "P2") (pin "10") (pinfunction "10_10") (pintype "passive"))
    )
    (net (code "112") (name "unconnected-(X1-NC-Pad1)") (class "Default")
      (node (ref "X1") (pin "1") (pinfunction "NC_1") (pintype "passive+no_connect"))
    )
  )
)
